# DRS4_ADC.net
KiCad netlist of a schematic drawn in Altium Designer
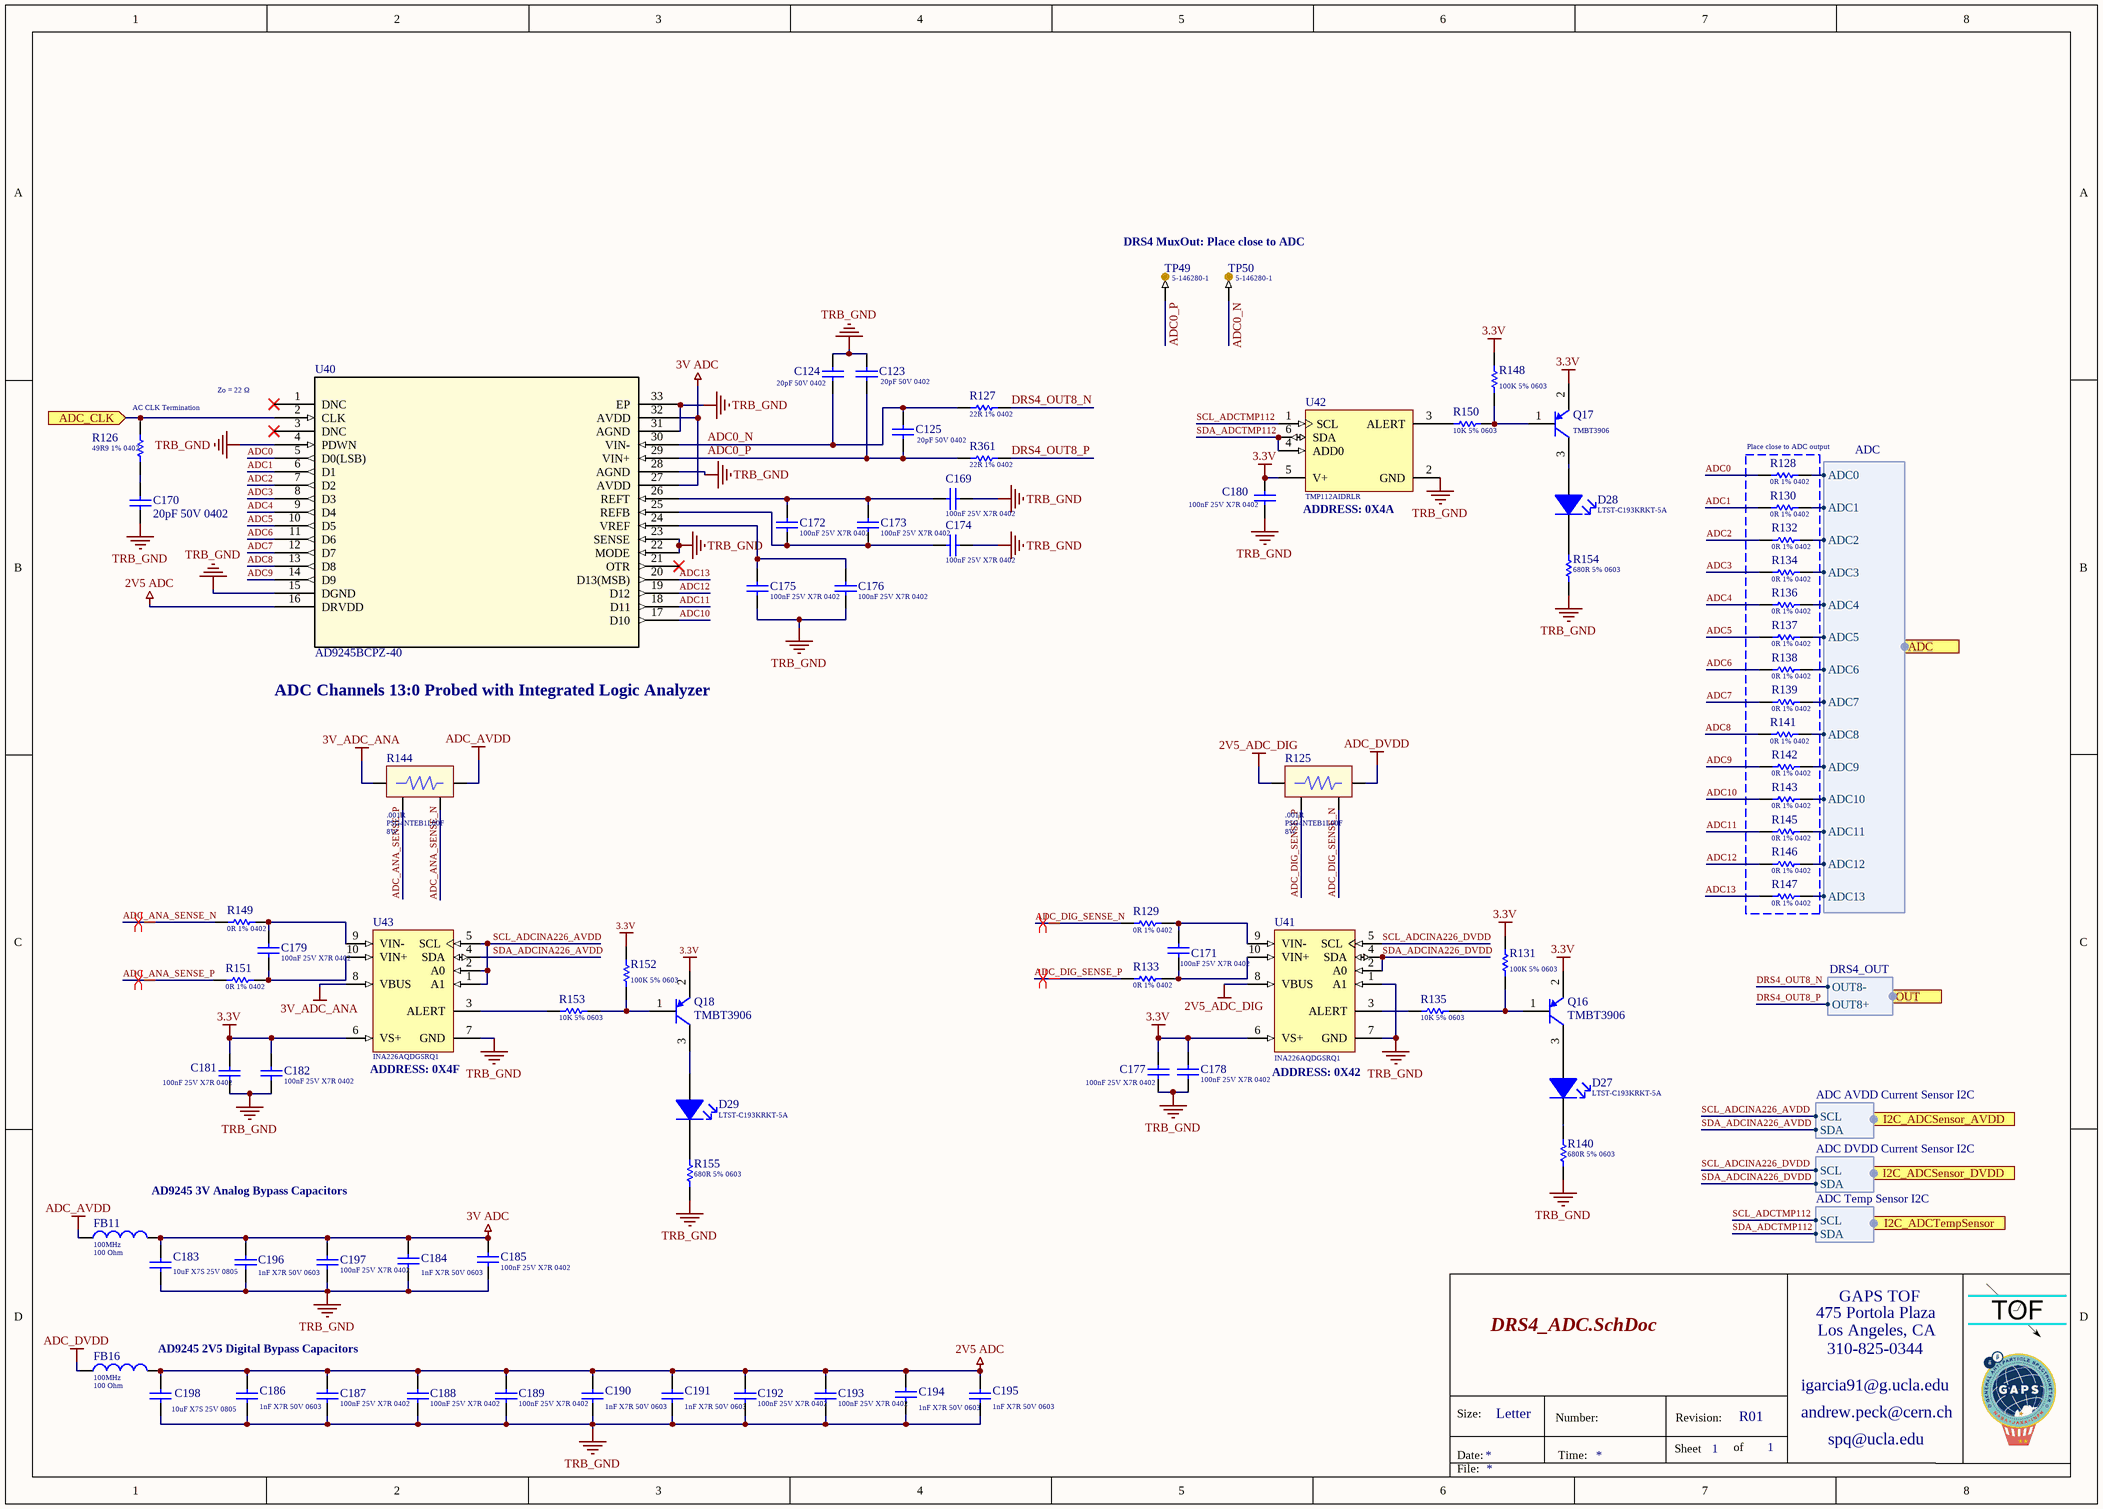
[diagram p0: DRS4_ADC.SchDoc]

(export (version "E")
  (design (tool "Eeschema 10.0.6"))
  (components
    (comp (ref "C123")
      (value "Cap_Murata_GJM1555C1H200GB01D_20pF")
      (footprint "Cap_Murata_GJM1555C1H200GB01D_20pF")
      (description "Multilayer Ceramic Capacitors MLCC - SMD/SMT 0402 20pF 50Volts C0G 2%")
      (fields (field (name "CAPACITANCE") "20pF 50V 0402"))
      (libsource (lib "Cap_Murata_GJM1555C1H200GB01D_20pF") (part "Cap_Murata_GJM1555C1H200GB01D_20pF"))
    )
    (comp (ref "C124")
      (value "Cap_Murata_GJM1555C1H200GB01D_20pF")
      (footprint "Cap_Murata_GJM1555C1H200GB01D_20pF")
      (description "Multilayer Ceramic Capacitors MLCC - SMD/SMT 0402 20pF 50Volts C0G 2%")
      (fields (field (name "CAPACITANCE") "20pF 50V 0402"))
      (libsource (lib "Cap_Murata_GJM1555C1H200GB01D_20pF") (part "Cap_Murata_GJM1555C1H200GB01D_20pF"))
    )
    (comp (ref "C125")
      (value "Cap_Murata_GJM1555C1H200GB01D_20pF")
      (footprint "Cap_Murata_GJM1555C1H200GB01D_20pF")
      (description "Multilayer Ceramic Capacitors MLCC - SMD/SMT 0402 20pF 50Volts C0G 2%")
      (fields (field (name "CAPACITANCE") "20pF 50V 0402"))
      (libsource (lib "Cap_Murata_GJM1555C1H200GB01D_20pF") (part "Cap_Murata_GJM1555C1H200GB01D_20pF"))
    )
    (comp (ref "C169")
      (value "Cap_Taiyo_Yuden_TMK105B7104KV-FR_100nF")
      (footprint "Cap_Taiyo_Yuden_TMK105B7104KV-FR_100nF")
      (description "CAP CER 100nF 25V X7R 0402")
      (fields (field (name "CAPACITANCE") "100nF 25V X7R 0402"))
      (libsource (lib "Cap_Taiyo_Yuden_TMK105B7104KV-FR_100nF") (part "Cap_Taiyo_Yuden_TMK105B7104KV-FR_100nF"))
    )
    (comp (ref "C170")
      (value "Cap_Murata_GJM1555C1H200GB01D_20pF")
      (footprint "Cap_Murata_GJM1555C1H200GB01D_20pF")
      (description "Multilayer Ceramic Capacitors MLCC - SMD/SMT 0402 20pF 50Volts C0G 2%")
      (fields (field (name "CAPACITANCE") "20pF 50V 0402"))
      (libsource (lib "Cap_Murata_GJM1555C1H200GB01D_20pF") (part "Cap_Murata_GJM1555C1H200GB01D_20pF"))
    )
    (comp (ref "C171")
      (value "Cap_Taiyo_Yuden_TMK105B7104KV-FR_100nF")
      (footprint "Cap_Taiyo_Yuden_TMK105B7104KV-FR_100nF")
      (description "CAP CER 100nF 25V X7R 0402")
      (fields (field (name "CAPACITANCE") "100nF 25V X7R 0402"))
      (libsource (lib "Cap_Taiyo_Yuden_TMK105B7104KV-FR_100nF") (part "Cap_Taiyo_Yuden_TMK105B7104KV-FR_100nF"))
    )
    (comp (ref "C172")
      (value "Cap_Taiyo_Yuden_TMK105B7104KV-FR_100nF")
      (footprint "Cap_Taiyo_Yuden_TMK105B7104KV-FR_100nF")
      (description "CAP CER 100nF 25V X7R 0402")
      (fields (field (name "CAPACITANCE") "100nF 25V X7R 0402"))
      (libsource (lib "Cap_Taiyo_Yuden_TMK105B7104KV-FR_100nF") (part "Cap_Taiyo_Yuden_TMK105B7104KV-FR_100nF"))
    )
    (comp (ref "C173")
      (value "Cap_Taiyo_Yuden_TMK105B7104KV-FR_100nF")
      (footprint "Cap_Taiyo_Yuden_TMK105B7104KV-FR_100nF")
      (description "CAP CER 100nF 25V X7R 0402")
      (fields (field (name "CAPACITANCE") "100nF 25V X7R 0402"))
      (libsource (lib "Cap_Taiyo_Yuden_TMK105B7104KV-FR_100nF") (part "Cap_Taiyo_Yuden_TMK105B7104KV-FR_100nF"))
    )
    (comp (ref "C174")
      (value "Cap_Taiyo_Yuden_TMK105B7104KV-FR_100nF")
      (footprint "Cap_Taiyo_Yuden_TMK105B7104KV-FR_100nF")
      (description "CAP CER 100nF 25V X7R 0402")
      (fields (field (name "CAPACITANCE") "100nF 25V X7R 0402"))
      (libsource (lib "Cap_Taiyo_Yuden_TMK105B7104KV-FR_100nF") (part "Cap_Taiyo_Yuden_TMK105B7104KV-FR_100nF"))
    )
    (comp (ref "C175")
      (value "Cap_Taiyo_Yuden_TMK105B7104KV-FR_100nF")
      (footprint "Cap_Taiyo_Yuden_TMK105B7104KV-FR_100nF")
      (description "CAP CER 100nF 25V X7R 0402")
      (fields (field (name "CAPACITANCE") "100nF 25V X7R 0402"))
      (libsource (lib "Cap_Taiyo_Yuden_TMK105B7104KV-FR_100nF") (part "Cap_Taiyo_Yuden_TMK105B7104KV-FR_100nF"))
    )
    (comp (ref "C176")
      (value "Cap_Taiyo_Yuden_TMK105B7104KV-FR_100nF")
      (footprint "Cap_Taiyo_Yuden_TMK105B7104KV-FR_100nF")
      (description "CAP CER 100nF 25V X7R 0402")
      (fields (field (name "CAPACITANCE") "100nF 25V X7R 0402"))
      (libsource (lib "Cap_Taiyo_Yuden_TMK105B7104KV-FR_100nF") (part "Cap_Taiyo_Yuden_TMK105B7104KV-FR_100nF"))
    )
    (comp (ref "C177")
      (value "Cap_Taiyo_Yuden_TMK105B7104KV-FR_100nF")
      (footprint "Cap_Taiyo_Yuden_TMK105B7104KV-FR_100nF")
      (description "CAP CER 100nF 25V X7R 0402")
      (fields (field (name "CAPACITANCE") "100nF 25V X7R 0402"))
      (libsource (lib "Cap_Taiyo_Yuden_TMK105B7104KV-FR_100nF") (part "Cap_Taiyo_Yuden_TMK105B7104KV-FR_100nF"))
    )
    (comp (ref "C178")
      (value "Cap_Taiyo_Yuden_TMK105B7104KV-FR_100nF")
      (footprint "Cap_Taiyo_Yuden_TMK105B7104KV-FR_100nF")
      (description "CAP CER 100nF 25V X7R 0402")
      (fields (field (name "CAPACITANCE") "100nF 25V X7R 0402"))
      (libsource (lib "Cap_Taiyo_Yuden_TMK105B7104KV-FR_100nF") (part "Cap_Taiyo_Yuden_TMK105B7104KV-FR_100nF"))
    )
    (comp (ref "C179")
      (value "Cap_Taiyo_Yuden_TMK105B7104KV-FR_100nF")
      (footprint "Cap_Taiyo_Yuden_TMK105B7104KV-FR_100nF")
      (description "CAP CER 100nF 25V X7R 0402")
      (fields (field (name "CAPACITANCE") "100nF 25V X7R 0402"))
      (libsource (lib "Cap_Taiyo_Yuden_TMK105B7104KV-FR_100nF") (part "Cap_Taiyo_Yuden_TMK105B7104KV-FR_100nF"))
    )
    (comp (ref "C180")
      (value "Cap_Taiyo_Yuden_TMK105B7104KV-FR_100nF")
      (footprint "Cap_Taiyo_Yuden_TMK105B7104KV-FR_100nF")
      (description "CAP CER 100nF 25V X7R 0402")
      (fields (field (name "CAPACITANCE") "100nF 25V X7R 0402"))
      (libsource (lib "Cap_Taiyo_Yuden_TMK105B7104KV-FR_100nF") (part "Cap_Taiyo_Yuden_TMK105B7104KV-FR_100nF"))
    )
    (comp (ref "C181")
      (value "Cap_Taiyo_Yuden_TMK105B7104KV-FR_100nF")
      (footprint "Cap_Taiyo_Yuden_TMK105B7104KV-FR_100nF")
      (description "CAP CER 100nF 25V X7R 0402")
      (fields (field (name "CAPACITANCE") "100nF 25V X7R 0402"))
      (libsource (lib "Cap_Taiyo_Yuden_TMK105B7104KV-FR_100nF") (part "Cap_Taiyo_Yuden_TMK105B7104KV-FR_100nF"))
    )
    (comp (ref "C182")
      (value "Cap_Taiyo_Yuden_TMK105B7104KV-FR_100nF")
      (footprint "Cap_Taiyo_Yuden_TMK105B7104KV-FR_100nF")
      (description "CAP CER 100nF 25V X7R 0402")
      (fields (field (name "CAPACITANCE") "100nF 25V X7R 0402"))
      (libsource (lib "Cap_Taiyo_Yuden_TMK105B7104KV-FR_100nF") (part "Cap_Taiyo_Yuden_TMK105B7104KV-FR_100nF"))
    )
    (comp (ref "C183")
      (value "Cap_Murata_ GRM21BC71E106ME11L_10uF")
      (footprint "Cap_Murata_ GRM21BC71E106ME11L_10uF")
      (description "CAP CER 10uF 25V X7R 0805")
      (fields (field (name "CAPACITANCE") "10uF X7S 25V 0805"))
      (libsource (lib "Cap_Murata_ GRM21BC71E106ME11L_10uF") (part "Cap_Murata_ GRM21BC71E106ME11L_10uF"))
    )
    (comp (ref "C184")
      (value "Cap_Kemet_C0603C102J5RACAUTO_1nF")
      (footprint "Cap_Kemet_C0603C102J5RACAUTO_1nF")
      (description "CAP CER 1nF 50V X7R 0603")
      (fields (field (name "CAPACITANCE") "1nF X7R 50V 0603"))
      (libsource (lib "Cap_Kemet_C0603C102J5RACAUTO_1nF") (part "Cap_Kemet_C0603C102J5RACAUTO_1nF"))
    )
    (comp (ref "C185")
      (value "Cap_Taiyo_Yuden_TMK105B7104KV-FR_100nF")
      (footprint "Cap_Taiyo_Yuden_TMK105B7104KV-FR_100nF")
      (description "CAP CER 100nF 25V X7R 0402")
      (fields (field (name "CAPACITANCE") "100nF 25V X7R 0402"))
      (libsource (lib "Cap_Taiyo_Yuden_TMK105B7104KV-FR_100nF") (part "Cap_Taiyo_Yuden_TMK105B7104KV-FR_100nF"))
    )
    (comp (ref "C186")
      (value "Cap_Kemet_C0603C102J5RACAUTO_1nF")
      (footprint "Cap_Kemet_C0603C102J5RACAUTO_1nF")
      (description "CAP CER 1nF 50V X7R 0603")
      (fields (field (name "CAPACITANCE") "1nF X7R 50V 0603"))
      (libsource (lib "Cap_Kemet_C0603C102J5RACAUTO_1nF") (part "Cap_Kemet_C0603C102J5RACAUTO_1nF"))
    )
    (comp (ref "C187")
      (value "Cap_Taiyo_Yuden_TMK105B7104KV-FR_100nF")
      (footprint "Cap_Taiyo_Yuden_TMK105B7104KV-FR_100nF")
      (description "CAP CER 100nF 25V X7R 0402")
      (fields (field (name "CAPACITANCE") "100nF 25V X7R 0402"))
      (libsource (lib "Cap_Taiyo_Yuden_TMK105B7104KV-FR_100nF") (part "Cap_Taiyo_Yuden_TMK105B7104KV-FR_100nF"))
    )
    (comp (ref "C188")
      (value "Cap_Taiyo_Yuden_TMK105B7104KV-FR_100nF")
      (footprint "Cap_Taiyo_Yuden_TMK105B7104KV-FR_100nF")
      (description "CAP CER 100nF 25V X7R 0402")
      (fields (field (name "CAPACITANCE") "100nF 25V X7R 0402"))
      (libsource (lib "Cap_Taiyo_Yuden_TMK105B7104KV-FR_100nF") (part "Cap_Taiyo_Yuden_TMK105B7104KV-FR_100nF"))
    )
    (comp (ref "C189")
      (value "Cap_Taiyo_Yuden_TMK105B7104KV-FR_100nF")
      (footprint "Cap_Taiyo_Yuden_TMK105B7104KV-FR_100nF")
      (description "CAP CER 100nF 25V X7R 0402")
      (fields (field (name "CAPACITANCE") "100nF 25V X7R 0402"))
      (libsource (lib "Cap_Taiyo_Yuden_TMK105B7104KV-FR_100nF") (part "Cap_Taiyo_Yuden_TMK105B7104KV-FR_100nF"))
    )
    (comp (ref "C190")
      (value "Cap_Kemet_C0603C102J5RACAUTO_1nF")
      (footprint "Cap_Kemet_C0603C102J5RACAUTO_1nF")
      (description "CAP CER 1nF 50V X7R 0603")
      (fields (field (name "CAPACITANCE") "1nF X7R 50V 0603"))
      (libsource (lib "Cap_Kemet_C0603C102J5RACAUTO_1nF") (part "Cap_Kemet_C0603C102J5RACAUTO_1nF"))
    )
    (comp (ref "C191")
      (value "Cap_Kemet_C0603C102J5RACAUTO_1nF")
      (footprint "Cap_Kemet_C0603C102J5RACAUTO_1nF")
      (description "CAP CER 1nF 50V X7R 0603")
      (fields (field (name "CAPACITANCE") "1nF X7R 50V 0603"))
      (libsource (lib "Cap_Kemet_C0603C102J5RACAUTO_1nF") (part "Cap_Kemet_C0603C102J5RACAUTO_1nF"))
    )
    (comp (ref "C192")
      (value "Cap_Taiyo_Yuden_TMK105B7104KV-FR_100nF")
      (footprint "Cap_Taiyo_Yuden_TMK105B7104KV-FR_100nF")
      (description "CAP CER 100nF 25V X7R 0402")
      (fields (field (name "CAPACITANCE") "100nF 25V X7R 0402"))
      (libsource (lib "Cap_Taiyo_Yuden_TMK105B7104KV-FR_100nF") (part "Cap_Taiyo_Yuden_TMK105B7104KV-FR_100nF"))
    )
    (comp (ref "C193")
      (value "Cap_Taiyo_Yuden_TMK105B7104KV-FR_100nF")
      (footprint "Cap_Taiyo_Yuden_TMK105B7104KV-FR_100nF")
      (description "CAP CER 100nF 25V X7R 0402")
      (fields (field (name "CAPACITANCE") "100nF 25V X7R 0402"))
      (libsource (lib "Cap_Taiyo_Yuden_TMK105B7104KV-FR_100nF") (part "Cap_Taiyo_Yuden_TMK105B7104KV-FR_100nF"))
    )
    (comp (ref "C194")
      (value "Cap_Kemet_C0603C102J5RACAUTO_1nF")
      (footprint "Cap_Kemet_C0603C102J5RACAUTO_1nF")
      (description "CAP CER 1nF 50V X7R 0603")
      (fields (field (name "CAPACITANCE") "1nF X7R 50V 0603"))
      (libsource (lib "Cap_Kemet_C0603C102J5RACAUTO_1nF") (part "Cap_Kemet_C0603C102J5RACAUTO_1nF"))
    )
    (comp (ref "C195")
      (value "Cap_Kemet_C0603C102J5RACAUTO_1nF")
      (footprint "Cap_Kemet_C0603C102J5RACAUTO_1nF")
      (description "CAP CER 1nF 50V X7R 0603")
      (fields (field (name "CAPACITANCE") "1nF X7R 50V 0603"))
      (libsource (lib "Cap_Kemet_C0603C102J5RACAUTO_1nF") (part "Cap_Kemet_C0603C102J5RACAUTO_1nF"))
    )
    (comp (ref "C196")
      (value "Cap_Kemet_C0603C102J5RACAUTO_1nF")
      (footprint "Cap_Kemet_C0603C102J5RACAUTO_1nF")
      (description "CAP CER 1nF 50V X7R 0603")
      (fields (field (name "CAPACITANCE") "1nF X7R 50V 0603"))
      (libsource (lib "Cap_Kemet_C0603C102J5RACAUTO_1nF") (part "Cap_Kemet_C0603C102J5RACAUTO_1nF"))
    )
    (comp (ref "C197")
      (value "Cap_Taiyo_Yuden_TMK105B7104KV-FR_100nF")
      (footprint "Cap_Taiyo_Yuden_TMK105B7104KV-FR_100nF")
      (description "CAP CER 100nF 25V X7R 0402")
      (fields (field (name "CAPACITANCE") "100nF 25V X7R 0402"))
      (libsource (lib "Cap_Taiyo_Yuden_TMK105B7104KV-FR_100nF") (part "Cap_Taiyo_Yuden_TMK105B7104KV-FR_100nF"))
    )
    (comp (ref "C198")
      (value "Cap_Murata_ GRM21BC71E106ME11L_10uF")
      (footprint "Cap_Murata_ GRM21BC71E106ME11L_10uF")
      (description "CAP CER 10uF 25V X7R 0805")
      (fields (field (name "CAPACITANCE") "10uF X7S 25V 0805"))
      (libsource (lib "Cap_Murata_ GRM21BC71E106ME11L_10uF") (part "Cap_Murata_ GRM21BC71E106ME11L_10uF"))
    )
    (comp (ref "D27")
      (value "LTST-C193KRKT-5A")
      (footprint "Led_Lite-On_LTST-C193KGKT-5A_Red")
      (description "Standard LEDs - SMD Red 470nm 28mcd 20mA")
      (fields (field (name "SERIES") "LTST-C193KRKT-5A"))
      (libsource (lib "Led_Lite-On_LTST-C193KGKT-5A_Red") (part "Led_Lite-On_LTST-C193KGKT-5A_Red"))
    )
    (comp (ref "D28")
      (value "LTST-C193KRKT-5A")
      (footprint "Led_Lite-On_LTST-C193KGKT-5A_Red")
      (description "Standard LEDs - SMD Red 470nm 28mcd 20mA")
      (fields (field (name "SERIES") "LTST-C193KRKT-5A"))
      (libsource (lib "Led_Lite-On_LTST-C193KGKT-5A_Red") (part "Led_Lite-On_LTST-C193KGKT-5A_Red"))
    )
    (comp (ref "D29")
      (value "LTST-C193KRKT-5A")
      (footprint "Led_Lite-On_LTST-C193KGKT-5A_Red")
      (description "Standard LEDs - SMD Red 470nm 28mcd 20mA")
      (fields (field (name "SERIES") "LTST-C193KRKT-5A"))
      (libsource (lib "Led_Lite-On_LTST-C193KGKT-5A_Red") (part "Led_Lite-On_LTST-C193KGKT-5A_Red"))
    )
    (comp (ref "FB11")
      (value "742792731")
      (footprint "FB_Wurth_Electronics_742792731_100Ohms")
      (description "FB SMD 100 OHM 25% 1.2A 0402")
      (fields (field (name "MEASURING FREQUENCY") "100MHz") (field (name "IMPEDANCE") "100 Ohm"))
      (libsource (lib "FB_Wurth_Electronics_742792731_100Ohms") (part "FB_Wurth_Electronics_742792731_100Ohms"))
    )
    (comp (ref "FB16")
      (value "742792731")
      (footprint "FB_Wurth_Electronics_742792731_100Ohms")
      (description "FB SMD 100 OHM 25% 1.2A 0402")
      (fields (field (name "MEASURING FREQUENCY") "100MHz") (field (name "IMPEDANCE") "100 Ohm"))
      (libsource (lib "FB_Wurth_Electronics_742792731_100Ohms") (part "FB_Wurth_Electronics_742792731_100Ohms"))
    )
    (comp (ref "Q16")
      (value "BJT_PNP_Toshiba_TMBT3906")
      (footprint "BJT_PNP_Toshiba_TMBT3906")
      (description "Bipolar Transistors - BJT Transistor for Low Freq. Amplification")
      (fields (field (name "SERIES") "TMBT3906"))
      (libsource (lib "BJT_PNP_Toshiba_TMBT3906") (part "BJT_PNP_Toshiba_TMBT3906"))
    )
    (comp (ref "Q17")
      (value "BJT_PNP_Toshiba_TMBT3906")
      (footprint "BJT_PNP_Toshiba_TMBT3906")
      (description "Bipolar Transistors - BJT Transistor for Low Freq. Amplification")
      (fields (field (name "SERIES") "TMBT3906"))
      (libsource (lib "BJT_PNP_Toshiba_TMBT3906") (part "BJT_PNP_Toshiba_TMBT3906"))
    )
    (comp (ref "Q18")
      (value "BJT_PNP_Toshiba_TMBT3906")
      (footprint "BJT_PNP_Toshiba_TMBT3906")
      (description "Bipolar Transistors - BJT Transistor for Low Freq. Amplification")
      (fields (field (name "SERIES") "TMBT3906"))
      (libsource (lib "BJT_PNP_Toshiba_TMBT3906") (part "BJT_PNP_Toshiba_TMBT3906"))
    )
    (comp (ref "R125")
      (value "SRes_KOA_PSG4NTEB1L00F_1mOhm")
      (footprint "SRes_KOA_PSG4NTEB1L00F_1mOhm")
      (description "Current Sense Resistors - SMD 1mOhm 8W 1% 50ppm AEC-Q200 Power Shunt")
      (fields
        (field (name "RESISTANCE") ".001R")
        (field (name "SERIES") "PSG4NTEB1L00F")
        (field (name "PARAMETER 1") "8W")
      )
      (libsource (lib "SRes_KOA_PSG4NTEB1L00F_1mOhm") (part "SRes_KOA_PSG4NTEB1L00F_1mOhm"))
    )
    (comp (ref "R126")
      (value "49R9 1% 0402")
      (footprint "RESC0402(1005)_L")
      (description "49R9 0.063W 1% 0402 (1005 Metric)  SMD")
      (fields (field (name "POWER") "0.063 W") (field (name "TOLERANCE") "1 %"))
      (libsource (lib "Altium Content Vault") (part "RES"))
    )
    (comp (ref "R127")
      (value "22R 1% 0402")
      (footprint "RESC0402(1005)_L")
      (description "22R 0.063W 1% 0402 (1005 Metric)  SMD")
      (fields (field (name "TOLERANCE") "1 %") (field (name "POWER") "0.063 W"))
      (libsource (lib "Altium Content Vault") (part "RES"))
    )
    (comp (ref "R128")
      (value "Res_Vishay_CRCW04020000Z0EDC_0_Ohm")
      (footprint "Res_Vishay_CRCW04020000Z0EDC_0_Ohm")
      (description "0R 0.062W 1% 0402 (1005 Metric)  SMD")
      (fields (field (name "RESISTANCE") "0R 1% 0402"))
      (libsource (lib "Res_Vishay_CRCW04020000Z0EDC_0_Ohm") (part "Res_Vishay_CRCW04020000Z0EDC_0_Ohm"))
    )
    (comp (ref "R129")
      (value "Res_Vishay_CRCW04020000Z0EDC_0_Ohm")
      (footprint "Res_Vishay_CRCW04020000Z0EDC_0_Ohm")
      (description "0R 0.062W 1% 0402 (1005 Metric)  SMD")
      (fields (field (name "RESISTANCE") "0R 1% 0402"))
      (libsource (lib "Res_Vishay_CRCW04020000Z0EDC_0_Ohm") (part "Res_Vishay_CRCW04020000Z0EDC_0_Ohm"))
    )
    (comp (ref "R130")
      (value "Res_Vishay_CRCW04020000Z0EDC_0_Ohm")
      (footprint "Res_Vishay_CRCW04020000Z0EDC_0_Ohm")
      (description "0R 0.062W 1% 0402 (1005 Metric)  SMD")
      (fields (field (name "RESISTANCE") "0R 1% 0402"))
      (libsource (lib "Res_Vishay_CRCW04020000Z0EDC_0_Ohm") (part "Res_Vishay_CRCW04020000Z0EDC_0_Ohm"))
    )
    (comp (ref "R131")
      (value "100K 5% 0603")
      (footprint "RESC0603(1608)_N")
      (description "100K 0.1W 5% 0603 (1608 Metric)  SMD")
      (fields (field (name "TOLERANCE") "5 %") (field (name "POWER") "0.1 W"))
      (libsource (lib "Altium Content Vault") (part "RES"))
    )
    (comp (ref "R132")
      (value "Res_Vishay_CRCW04020000Z0EDC_0_Ohm")
      (footprint "Res_Vishay_CRCW04020000Z0EDC_0_Ohm")
      (description "0R 0.062W 1% 0402 (1005 Metric)  SMD")
      (fields (field (name "RESISTANCE") "0R 1% 0402"))
      (libsource (lib "Res_Vishay_CRCW04020000Z0EDC_0_Ohm") (part "Res_Vishay_CRCW04020000Z0EDC_0_Ohm"))
    )
    (comp (ref "R133")
      (value "Res_Vishay_CRCW04020000Z0EDC_0_Ohm")
      (footprint "Res_Vishay_CRCW04020000Z0EDC_0_Ohm")
      (description "0R 0.062W 1% 0402 (1005 Metric)  SMD")
      (fields (field (name "RESISTANCE") "0R 1% 0402"))
      (libsource (lib "Res_Vishay_CRCW04020000Z0EDC_0_Ohm") (part "Res_Vishay_CRCW04020000Z0EDC_0_Ohm"))
    )
    (comp (ref "R134")
      (value "Res_Vishay_CRCW04020000Z0EDC_0_Ohm")
      (footprint "Res_Vishay_CRCW04020000Z0EDC_0_Ohm")
      (description "0R 0.062W 1% 0402 (1005 Metric)  SMD")
      (fields (field (name "RESISTANCE") "0R 1% 0402"))
      (libsource (lib "Res_Vishay_CRCW04020000Z0EDC_0_Ohm") (part "Res_Vishay_CRCW04020000Z0EDC_0_Ohm"))
    )
    (comp (ref "R135")
      (value "10K 5% 0603")
      (footprint "RESC0603(1608)_L")
      (description "10K 0.1W 5% 0603 (1608 Metric)  SMD")
      (fields (field (name "TOLERANCE") "5 %") (field (name "POWER") "0.1 W"))
      (libsource (lib "Altium Content Vault") (part "RES"))
    )
    (comp (ref "R136")
      (value "Res_Vishay_CRCW04020000Z0EDC_0_Ohm")
      (footprint "Res_Vishay_CRCW04020000Z0EDC_0_Ohm")
      (description "0R 0.062W 1% 0402 (1005 Metric)  SMD")
      (fields (field (name "RESISTANCE") "0R 1% 0402"))
      (libsource (lib "Res_Vishay_CRCW04020000Z0EDC_0_Ohm") (part "Res_Vishay_CRCW04020000Z0EDC_0_Ohm"))
    )
    (comp (ref "R137")
      (value "Res_Vishay_CRCW04020000Z0EDC_0_Ohm")
      (footprint "Res_Vishay_CRCW04020000Z0EDC_0_Ohm")
      (description "0R 0.062W 1% 0402 (1005 Metric)  SMD")
      (fields (field (name "RESISTANCE") "0R 1% 0402"))
      (libsource (lib "Res_Vishay_CRCW04020000Z0EDC_0_Ohm") (part "Res_Vishay_CRCW04020000Z0EDC_0_Ohm"))
    )
    (comp (ref "R138")
      (value "Res_Vishay_CRCW04020000Z0EDC_0_Ohm")
      (footprint "Res_Vishay_CRCW04020000Z0EDC_0_Ohm")
      (description "0R 0.062W 1% 0402 (1005 Metric)  SMD")
      (fields (field (name "RESISTANCE") "0R 1% 0402"))
      (libsource (lib "Res_Vishay_CRCW04020000Z0EDC_0_Ohm") (part "Res_Vishay_CRCW04020000Z0EDC_0_Ohm"))
    )
    (comp (ref "R139")
      (value "Res_Vishay_CRCW04020000Z0EDC_0_Ohm")
      (footprint "Res_Vishay_CRCW04020000Z0EDC_0_Ohm")
      (description "0R 0.062W 1% 0402 (1005 Metric)  SMD")
      (fields (field (name "RESISTANCE") "0R 1% 0402"))
      (libsource (lib "Res_Vishay_CRCW04020000Z0EDC_0_Ohm") (part "Res_Vishay_CRCW04020000Z0EDC_0_Ohm"))
    )
    (comp (ref "R140")
      (value "680R 5% 0603")
      (footprint "RESC0603(1608)_L")
      (description "680R 0.1W 5% 0603 (1608 Metric)  SMD")
      (fields (field (name "TOLERANCE") "5 %") (field (name "POWER") "0.1 W"))
      (libsource (lib "Altium Content Vault") (part "RES"))
    )
    (comp (ref "R141")
      (value "Res_Vishay_CRCW04020000Z0EDC_0_Ohm")
      (footprint "Res_Vishay_CRCW04020000Z0EDC_0_Ohm")
      (description "0R 0.062W 1% 0402 (1005 Metric)  SMD")
      (fields (field (name "RESISTANCE") "0R 1% 0402"))
      (libsource (lib "Res_Vishay_CRCW04020000Z0EDC_0_Ohm") (part "Res_Vishay_CRCW04020000Z0EDC_0_Ohm"))
    )
    (comp (ref "R142")
      (value "Res_Vishay_CRCW04020000Z0EDC_0_Ohm")
      (footprint "Res_Vishay_CRCW04020000Z0EDC_0_Ohm")
      (description "0R 0.062W 1% 0402 (1005 Metric)  SMD")
      (fields (field (name "RESISTANCE") "0R 1% 0402"))
      (libsource (lib "Res_Vishay_CRCW04020000Z0EDC_0_Ohm") (part "Res_Vishay_CRCW04020000Z0EDC_0_Ohm"))
    )
    (comp (ref "R143")
      (value "Res_Vishay_CRCW04020000Z0EDC_0_Ohm")
      (footprint "Res_Vishay_CRCW04020000Z0EDC_0_Ohm")
      (description "0R 0.062W 1% 0402 (1005 Metric)  SMD")
      (fields (field (name "RESISTANCE") "0R 1% 0402"))
      (libsource (lib "Res_Vishay_CRCW04020000Z0EDC_0_Ohm") (part "Res_Vishay_CRCW04020000Z0EDC_0_Ohm"))
    )
    (comp (ref "R144")
      (value "SRes_KOA_PSG4NTEB1L00F_1mOhm")
      (footprint "SRes_KOA_PSG4NTEB1L00F_1mOhm")
      (description "Current Sense Resistors - SMD 1mOhm 8W 1% 50ppm AEC-Q200 Power Shunt")
      (fields
        (field (name "RESISTANCE") ".001R")
        (field (name "SERIES") "PSG4NTEB1L00F")
        (field (name "PARAMETER 1") "8W")
      )
      (libsource (lib "SRes_KOA_PSG4NTEB1L00F_1mOhm") (part "SRes_KOA_PSG4NTEB1L00F_1mOhm"))
    )
    (comp (ref "R145")
      (value "Res_Vishay_CRCW04020000Z0EDC_0_Ohm")
      (footprint "Res_Vishay_CRCW04020000Z0EDC_0_Ohm")
      (description "0R 0.062W 1% 0402 (1005 Metric)  SMD")
      (fields (field (name "RESISTANCE") "0R 1% 0402"))
      (libsource (lib "Res_Vishay_CRCW04020000Z0EDC_0_Ohm") (part "Res_Vishay_CRCW04020000Z0EDC_0_Ohm"))
    )
    (comp (ref "R146")
      (value "Res_Vishay_CRCW04020000Z0EDC_0_Ohm")
      (footprint "Res_Vishay_CRCW04020000Z0EDC_0_Ohm")
      (description "0R 0.062W 1% 0402 (1005 Metric)  SMD")
      (fields (field (name "RESISTANCE") "0R 1% 0402"))
      (libsource (lib "Res_Vishay_CRCW04020000Z0EDC_0_Ohm") (part "Res_Vishay_CRCW04020000Z0EDC_0_Ohm"))
    )
    (comp (ref "R147")
      (value "Res_Vishay_CRCW04020000Z0EDC_0_Ohm")
      (footprint "Res_Vishay_CRCW04020000Z0EDC_0_Ohm")
      (description "0R 0.062W 1% 0402 (1005 Metric)  SMD")
      (fields (field (name "RESISTANCE") "0R 1% 0402"))
      (libsource (lib "Res_Vishay_CRCW04020000Z0EDC_0_Ohm") (part "Res_Vishay_CRCW04020000Z0EDC_0_Ohm"))
    )
    (comp (ref "R148")
      (value "100K 5% 0603")
      (footprint "RESC0603(1608)_N")
      (description "100K 0.1W 5% 0603 (1608 Metric)  SMD")
      (fields (field (name "TOLERANCE") "5 %") (field (name "POWER") "0.1 W"))
      (libsource (lib "Altium Content Vault") (part "RES"))
    )
    (comp (ref "R149")
      (value "Res_Vishay_CRCW04020000Z0EDC_0_Ohm")
      (footprint "Res_Vishay_CRCW04020000Z0EDC_0_Ohm")
      (description "0R 0.062W 1% 0402 (1005 Metric)  SMD")
      (fields (field (name "RESISTANCE") "0R 1% 0402"))
      (libsource (lib "Res_Vishay_CRCW04020000Z0EDC_0_Ohm") (part "Res_Vishay_CRCW04020000Z0EDC_0_Ohm"))
    )
    (comp (ref "R150")
      (value "10K 5% 0603")
      (footprint "RESC0603(1608)_L")
      (description "10K 0.1W 5% 0603 (1608 Metric)  SMD")
      (fields (field (name "TOLERANCE") "5 %") (field (name "POWER") "0.1 W"))
      (libsource (lib "Altium Content Vault") (part "RES"))
    )
    (comp (ref "R151")
      (value "Res_Vishay_CRCW04020000Z0EDC_0_Ohm")
      (footprint "Res_Vishay_CRCW04020000Z0EDC_0_Ohm")
      (description "0R 0.062W 1% 0402 (1005 Metric)  SMD")
      (fields (field (name "RESISTANCE") "0R 1% 0402"))
      (libsource (lib "Res_Vishay_CRCW04020000Z0EDC_0_Ohm") (part "Res_Vishay_CRCW04020000Z0EDC_0_Ohm"))
    )
    (comp (ref "R152")
      (value "100K 5% 0603")
      (footprint "RESC0603(1608)_N")
      (description "100K 0.1W 5% 0603 (1608 Metric)  SMD")
      (fields (field (name "TOLERANCE") "5 %") (field (name "POWER") "0.1 W"))
      (libsource (lib "Altium Content Vault") (part "RES"))
    )
    (comp (ref "R153")
      (value "10K 5% 0603")
      (footprint "RESC0603(1608)_L")
      (description "10K 0.1W 5% 0603 (1608 Metric)  SMD")
      (fields (field (name "TOLERANCE") "5 %") (field (name "POWER") "0.1 W"))
      (libsource (lib "Altium Content Vault") (part "RES"))
    )
    (comp (ref "R154")
      (value "680R 5% 0603")
      (footprint "RESC0603(1608)_L")
      (description "680R 0.1W 5% 0603 (1608 Metric)  SMD")
      (fields (field (name "TOLERANCE") "5 %") (field (name "POWER") "0.1 W"))
      (libsource (lib "Altium Content Vault") (part "RES"))
    )
    (comp (ref "R155")
      (value "680R 5% 0603")
      (footprint "RESC0603(1608)_L")
      (description "680R 0.1W 5% 0603 (1608 Metric)  SMD")
      (fields (field (name "TOLERANCE") "5 %") (field (name "POWER") "0.1 W"))
      (libsource (lib "Altium Content Vault") (part "RES"))
    )
    (comp (ref "R361")
      (value "22R 1% 0402")
      (footprint "RESC0402(1005)_L")
      (description "22R 0.063W 1% 0402 (1005 Metric)  SMD")
      (fields (field (name "TOLERANCE") "1 %") (field (name "POWER") "0.063 W"))
      (libsource (lib "Altium Content Vault") (part "RES"))
    )
    (comp (ref "TP49")
      (value "TP_TE_Connectivity_5-146280-1_1POS")
      (footprint "TP_TE_Connectivity_5-146280-1_1POS")
      (description "Headers & Wire Housings Unshrouded 1 POS T/H")
      (fields (field (name "SERIES") "5-146280-1"))
      (libsource (lib "TP_TE_Connectivity_5-146280-1_1POS") (part "TP_TE_Connectivity_5-146280-1_1POS"))
    )
    (comp (ref "TP50")
      (value "TP_TE_Connectivity_5-146280-1_1POS")
      (footprint "TP_TE_Connectivity_5-146280-1_1POS")
      (description "Headers & Wire Housings Unshrouded 1 POS T/H")
      (fields (field (name "SERIES") "5-146280-1"))
      (libsource (lib "TP_TE_Connectivity_5-146280-1_1POS") (part "TP_TE_Connectivity_5-146280-1_1POS"))
    )
    (comp (ref "U40")
      (value "AD9245")
      (footprint "CP_32_2")
      (description "Analog to Digital Converters - ADC 14-Bit 40 MSPS 3V")
      (fields (field (name "SERIES") "AD9245BCPZ-40") (field (name "PART") "AD9245BCPZ-40"))
      (libsource (lib "AD9245BCPZ-40") (part "AD9245BCPZ-40"))
    )
    (comp (ref "U41")
      (value "INA226AQDGSRQ1")
      (footprint "INA226AQDGSRQ1")
      (libsource (lib "INA226AQDGSRQ1") (part "INA226AQDGSRQ1"))
    )
    (comp (ref "U42")
      (value "TMP112AIDRLR")
      (footprint "TMP112AIDRLR")
      (description "Board Mount Temperature Sensors Hi-Prec Lo-Pwr Dig Temp Sensor")
      (libsource (lib "TMP112AIDRLR") (part "TMP112AIDRLR"))
    )
    (comp (ref "U43")
      (value "INA226AQDGSRQ1")
      (footprint "INA226AQDGSRQ1")
      (libsource (lib "INA226AQDGSRQ1") (part "INA226AQDGSRQ1"))
    )
  )
  (nets
    (net (code "9") (name "/ADC0") (class "Default")
      (node (ref "R128") (pin "1") (pinfunction "1_1") (pintype "passive"))
      (node (ref "U40") (pin "5") (pinfunction "D0(LSB)_5") (pintype "output"))
    )
    (net (code "10") (name "/ADC0_N") (class "Default")
      (node (ref "C124") (pin "1") (pinfunction "1_1") (pintype "passive"))
      (node (ref "C125") (pin "2") (pinfunction "2_2") (pintype "passive"))
      (node (ref "R127") (pin "2") (pinfunction "2_2") (pintype "passive"))
      (node (ref "TP50") (pin "1") (pinfunction "1_1") (pintype "input"))
      (node (ref "U40") (pin "30") (pinfunction "VIN-_30") (pintype "input"))
    )
    (net (code "11") (name "/ADC0_P") (class "Default")
      (node (ref "C123") (pin "1") (pinfunction "1_1") (pintype "passive"))
      (node (ref "C125") (pin "1") (pinfunction "1_1") (pintype "passive"))
      (node (ref "R361") (pin "2") (pinfunction "2_2") (pintype "passive"))
      (node (ref "TP49") (pin "1") (pinfunction "1_1") (pintype "input"))
      (node (ref "U40") (pin "29") (pinfunction "VIN+_29") (pintype "input"))
    )
    (net (code "12") (name "/ADC1") (class "Default")
      (node (ref "R130") (pin "1") (pinfunction "1_1") (pintype "passive"))
      (node (ref "U40") (pin "6") (pinfunction "D1_6") (pintype "output"))
    )
    (net (code "13") (name "/ADC2") (class "Default")
      (node (ref "R132") (pin "1") (pinfunction "1_1") (pintype "passive"))
      (node (ref "U40") (pin "7") (pinfunction "D2_7") (pintype "output"))
    )
    (net (code "14") (name "/ADC3") (class "Default")
      (node (ref "R134") (pin "1") (pinfunction "1_1") (pintype "passive"))
      (node (ref "U40") (pin "8") (pinfunction "D3_8") (pintype "output"))
    )
    (net (code "15") (name "/ADC4") (class "Default")
      (node (ref "R136") (pin "1") (pinfunction "1_1") (pintype "passive"))
      (node (ref "U40") (pin "9") (pinfunction "D4_9") (pintype "output"))
    )
    (net (code "16") (name "/ADC5") (class "Default")
      (node (ref "R137") (pin "1") (pinfunction "1_1") (pintype "passive"))
      (node (ref "U40") (pin "10") (pinfunction "D5_10") (pintype "output"))
    )
    (net (code "17") (name "/ADC6") (class "Default")
      (node (ref "R138") (pin "1") (pinfunction "1_1") (pintype "passive"))
      (node (ref "U40") (pin "11") (pinfunction "D6_11") (pintype "output"))
    )
    (net (code "18") (name "/ADC7") (class "Default")
      (node (ref "R139") (pin "1") (pinfunction "1_1") (pintype "passive"))
      (node (ref "U40") (pin "12") (pinfunction "D7_12") (pintype "output"))
    )
    (net (code "19") (name "/ADC8") (class "Default")
      (node (ref "R141") (pin "1") (pinfunction "1_1") (pintype "passive"))
      (node (ref "U40") (pin "13") (pinfunction "D8_13") (pintype "output"))
    )
    (net (code "20") (name "/ADC9") (class "Default")
      (node (ref "R142") (pin "1") (pinfunction "1_1") (pintype "passive"))
      (node (ref "U40") (pin "14") (pinfunction "D9_14") (pintype "output"))
    )
    (net (code "21") (name "/ADC10") (class "Default")
      (node (ref "R143") (pin "1") (pinfunction "1_1") (pintype "passive"))
      (node (ref "U40") (pin "17") (pinfunction "D10_17") (pintype "output"))
    )
    (net (code "22") (name "/ADC11") (class "Default")
      (node (ref "R145") (pin "1") (pinfunction "1_1") (pintype "passive"))
      (node (ref "U40") (pin "18") (pinfunction "D11_18") (pintype "output"))
    )
    (net (code "23") (name "/ADC12") (class "Default")
      (node (ref "R146") (pin "1") (pinfunction "1_1") (pintype "passive"))
      (node (ref "U40") (pin "19") (pinfunction "D12_19") (pintype "output"))
    )
    (net (code "24") (name "/ADC13") (class "Default")
      (node (ref "R147") (pin "1") (pinfunction "1_1") (pintype "passive"))
      (node (ref "U40") (pin "20") (pinfunction "D13(MSB)_20") (pintype "output"))
    )
    (net (code "25") (name "/ADC_ANA_SENSE_N") (class "Default")
      (node (ref "R144") (pin "3") (pinfunction "3_3") (pintype "passive"))
      (node (ref "R149") (pin "1") (pinfunction "1_1") (pintype "passive"))
    )
    (net (code "26") (name "/ADC_ANA_SENSE_P") (class "Default")
      (node (ref "R144") (pin "4") (pinfunction "4_4") (pintype "passive"))
      (node (ref "R151") (pin "1") (pinfunction "1_1") (pintype "passive"))
    )
    (net (code "27") (name "/ADC_CLK") (class "Default")
      (node (ref "R126") (pin "2") (pinfunction "2_2") (pintype "passive"))
      (node (ref "U40") (pin "2") (pinfunction "CLK_2") (pintype "input"))
    )
    (net (code "28") (name "/ADC_DIG_SENSE_N") (class "Default")
      (node (ref "R125") (pin "3") (pinfunction "3_3") (pintype "passive"))
      (node (ref "R129") (pin "1") (pinfunction "1_1") (pintype "passive"))
    )
    (net (code "29") (name "/ADC_DIG_SENSE_P") (class "Default")
      (node (ref "R125") (pin "4") (pinfunction "4_4") (pintype "passive"))
      (node (ref "R133") (pin "1") (pinfunction "1_1") (pintype "passive"))
    )
    (net (code "30") (name "/DRS4_OUT8_N") (class "Default")
      (node (ref "R127") (pin "1") (pinfunction "1_1") (pintype "passive"))
    )
    (net (code "31") (name "/DRS4_OUT8_P") (class "Default")
      (node (ref "R361") (pin "1") (pinfunction "1_1") (pintype "passive"))
    )
    (net (code "32") (name "/SCL_ADCINA226_AVDD") (class "Default")
      (node (ref "U43") (pin "1") (pinfunction "A1_1") (pintype "input"))
      (node (ref "U43") (pin "2") (pinfunction "A0_2") (pintype "input"))
      (node (ref "U43") (pin "5") (pinfunction "SCL_5") (pintype "input"))
    )
    (net (code "33") (name "/SCL_ADCINA226_DVDD") (class "Default")
      (node (ref "U41") (pin "5") (pinfunction "SCL_5") (pintype "input"))
    )
    (net (code "34") (name "/SCL_ADCTMP112") (class "Default")
      (node (ref "U42") (pin "1") (pinfunction "SCL_1") (pintype "input"))
    )
    (net (code "35") (name "/SDA_ADCINA226_AVDD") (class "Default")
      (node (ref "U43") (pin "4") (pinfunction "SDA_4") (pintype "bidirectional"))
    )
    (net (code "36") (name "/SDA_ADCINA226_DVDD") (class "Default")
      (node (ref "U41") (pin "2") (pinfunction "A0_2") (pintype "input"))
      (node (ref "U41") (pin "4") (pinfunction "SDA_4") (pintype "bidirectional"))
    )
    (net (code "37") (name "/SDA_ADCTMP112") (class "Default")
      (node (ref "U42") (pin "4") (pinfunction "ADD0_4") (pintype "input"))
      (node (ref "U42") (pin "6") (pinfunction "SDA_6") (pintype "bidirectional"))
    )
    (net (code "43") (name "2V5 ADC") (class "Default")
      (node (ref "C186") (pin "2") (pinfunction "2_2") (pintype "passive"))
      (node (ref "C187") (pin "1") (pinfunction "1_1") (pintype "passive"))
      (node (ref "C188") (pin "1") (pinfunction "1_1") (pintype "passive"))
      (node (ref "C189") (pin "1") (pinfunction "1_1") (pintype "passive"))
      (node (ref "C190") (pin "2") (pinfunction "2_2") (pintype "passive"))
      (node (ref "C191") (pin "2") (pinfunction "2_2") (pintype "passive"))
      (node (ref "C192") (pin "1") (pinfunction "1_1") (pintype "passive"))
      (node (ref "C193") (pin "1") (pinfunction "1_1") (pintype "passive"))
      (node (ref "C194") (pin "2") (pinfunction "2_2") (pintype "passive"))
      (node (ref "C195") (pin "2") (pinfunction "2_2") (pintype "passive"))
      (node (ref "C198") (pin "1") (pinfunction "1_1") (pintype "passive"))
      (node (ref "FB16") (pin "2") (pinfunction "2_2") (pintype "passive"))
      (node (ref "U40") (pin "16") (pinfunction "DRVDD_16") (pintype "power_in"))
    )
    (net (code "44") (name "2V5_ADC_DIG") (class "Default")
      (node (ref "R125") (pin "1") (pinfunction "1_1") (pintype "passive"))
      (node (ref "U41") (pin "8") (pinfunction "VBUS_8") (pintype "input"))
    )
    (net (code "45") (name "3.3V") (class "Default")
      (node (ref "C177") (pin "2") (pinfunction "2_2") (pintype "passive"))
      (node (ref "C178") (pin "2") (pinfunction "2_2") (pintype "passive"))
      (node (ref "C180") (pin "1") (pinfunction "1_1") (pintype "passive"))
      (node (ref "C181") (pin "2") (pinfunction "2_2") (pintype "passive"))
      (node (ref "C182") (pin "2") (pinfunction "2_2") (pintype "passive"))
      (node (ref "Q16") (pin "2") (pinfunction "E_2") (pintype "passive"))
      (node (ref "Q17") (pin "2") (pinfunction "E_2") (pintype "passive"))
      (node (ref "Q18") (pin "2") (pinfunction "E_2") (pintype "passive"))
      (node (ref "R131") (pin "2") (pinfunction "2_2") (pintype "passive"))
      (node (ref "R148") (pin "2") (pinfunction "2_2") (pintype "passive"))
      (node (ref "R152") (pin "2") (pinfunction "2_2") (pintype "passive"))
      (node (ref "U41") (pin "6") (pinfunction "VS+_6") (pintype "input"))
      (node (ref "U42") (pin "5") (pinfunction "V+_5") (pintype "power_in"))
      (node (ref "U43") (pin "6") (pinfunction "VS+_6") (pintype "input"))
    )
    (net (code "46") (name "3V ADC") (class "Default")
      (node (ref "C183") (pin "1") (pinfunction "1_1") (pintype "passive"))
      (node (ref "C184") (pin "2") (pinfunction "2_2") (pintype "passive"))
      (node (ref "C185") (pin "1") (pinfunction "1_1") (pintype "passive"))
      (node (ref "C196") (pin "2") (pinfunction "2_2") (pintype "passive"))
      (node (ref "C197") (pin "1") (pinfunction "1_1") (pintype "passive"))
      (node (ref "FB11") (pin "2") (pinfunction "2_2") (pintype "passive"))
      (node (ref "U40") (pin "27") (pinfunction "AVDD_27") (pintype "power_in"))
      (node (ref "U40") (pin "32") (pinfunction "AVDD_32") (pintype "power_in"))
    )
    (net (code "47") (name "3V_ADC_ANA") (class "Default")
      (node (ref "R144") (pin "1") (pinfunction "1_1") (pintype "passive"))
      (node (ref "U43") (pin "8") (pinfunction "VBUS_8") (pintype "input"))
    )
    (net (code "48") (name "ADC_AVDD") (class "Default")
      (node (ref "FB11") (pin "1") (pinfunction "1_1") (pintype "passive"))
      (node (ref "R144") (pin "2") (pinfunction "2_2") (pintype "passive"))
    )
    (net (code "49") (name "ADC_DVDD") (class "Default")
      (node (ref "FB16") (pin "1") (pinfunction "1_1") (pintype "passive"))
      (node (ref "R125") (pin "2") (pinfunction "2_2") (pintype "passive"))
    )
    (net (code "50") (name "Net-(C170-Pad2)") (class "Default")
      (node (ref "C170") (pin "2") (pinfunction "2_2") (pintype "passive"))
      (node (ref "R126") (pin "1") (pinfunction "1_1") (pintype "passive"))
    )
    (net (code "51") (name "Net-(D27-A)") (class "Default")
      (node (ref "D27") (pin "2") (pinfunction "A_2") (pintype "passive"))
      (node (ref "Q16") (pin "3") (pinfunction "C_3") (pintype "passive"))
    )
    (net (code "52") (name "Net-(D27-K)") (class "Default")
      (node (ref "D27") (pin "1") (pinfunction "K_1") (pintype "passive"))
      (node (ref "R140") (pin "2") (pinfunction "2_2") (pintype "passive"))
    )
    (net (code "53") (name "Net-(D28-A)") (class "Default")
      (node (ref "D28") (pin "2") (pinfunction "A_2") (pintype "passive"))
      (node (ref "Q17") (pin "3") (pinfunction "C_3") (pintype "passive"))
    )
    (net (code "54") (name "Net-(D28-K)") (class "Default")
      (node (ref "D28") (pin "1") (pinfunction "K_1") (pintype "passive"))
      (node (ref "R154") (pin "2") (pinfunction "2_2") (pintype "passive"))
    )
    (net (code "55") (name "Net-(D29-A)") (class "Default")
      (node (ref "D29") (pin "2") (pinfunction "A_2") (pintype "passive"))
      (node (ref "Q18") (pin "3") (pinfunction "C_3") (pintype "passive"))
    )
    (net (code "56") (name "Net-(D29-K)") (class "Default")
      (node (ref "D29") (pin "1") (pinfunction "K_1") (pintype "passive"))
      (node (ref "R155") (pin "2") (pinfunction "2_2") (pintype "passive"))
    )
    (net (code "57") (name "Net-(Q16-B)") (class "Default")
      (node (ref "Q16") (pin "1") (pinfunction "B_1") (pintype "passive"))
      (node (ref "R131") (pin "1") (pinfunction "1_1") (pintype "passive"))
      (node (ref "R135") (pin "1") (pinfunction "1_1") (pintype "passive"))
    )
    (net (code "58") (name "Net-(Q17-B)") (class "Default")
      (node (ref "Q17") (pin "1") (pinfunction "B_1") (pintype "passive"))
      (node (ref "R148") (pin "1") (pinfunction "1_1") (pintype "passive"))
      (node (ref "R150") (pin "1") (pinfunction "1_1") (pintype "passive"))
    )
    (net (code "59") (name "Net-(Q18-B)") (class "Default")
      (node (ref "Q18") (pin "1") (pinfunction "B_1") (pintype "passive"))
      (node (ref "R152") (pin "1") (pinfunction "1_1") (pintype "passive"))
      (node (ref "R153") (pin "1") (pinfunction "1_1") (pintype "passive"))
    )
    (net (code "60") (name "Net-(U40-REFB)") (class "Default")
      (node (ref "C172") (pin "2") (pinfunction "2_2") (pintype "passive"))
      (node (ref "C173") (pin "2") (pinfunction "2_2") (pintype "passive"))
      (node (ref "C174") (pin "2") (pinfunction "2_2") (pintype "passive"))
      (node (ref "U40") (pin "25") (pinfunction "REFB_25") (pintype "input"))
    )
    (net (code "61") (name "Net-(U40-REFT)") (class "Default")
      (node (ref "C169") (pin "2") (pinfunction "2_2") (pintype "passive"))
      (node (ref "C172") (pin "1") (pinfunction "1_1") (pintype "passive"))
      (node (ref "C173") (pin "1") (pinfunction "1_1") (pintype "passive"))
      (node (ref "U40") (pin "26") (pinfunction "REFT_26") (pintype "input"))
    )
    (net (code "62") (name "Net-(U40-VREF)") (class "Default")
      (node (ref "C175") (pin "1") (pinfunction "1_1") (pintype "passive"))
      (node (ref "C176") (pin "1") (pinfunction "1_1") (pintype "passive"))
      (node (ref "U40") (pin "24") (pinfunction "VREF_24") (pintype "input"))
    )
    (net (code "63") (name "Net-(U41-ALERT)") (class "Default")
      (node (ref "R135") (pin "2") (pinfunction "2_2") (pintype "passive"))
      (node (ref "U41") (pin "3") (pinfunction "ALERT_3") (pintype "open_collector"))
    )
    (net (code "64") (name "Net-(U41-VIN+)") (class "Default")
      (node (ref "C171") (pin "1") (pinfunction "1_1") (pintype "passive"))
      (node (ref "R133") (pin "2") (pinfunction "2_2") (pintype "passive"))
      (node (ref "U41") (pin "10") (pinfunction "VIN+_10") (pintype "input"))
    )
    (net (code "65") (name "Net-(U41-VIN-)") (class "Default")
      (node (ref "C171") (pin "2") (pinfunction "2_2") (pintype "passive"))
      (node (ref "R129") (pin "2") (pinfunction "2_2") (pintype "passive"))
      (node (ref "U41") (pin "9") (pinfunction "VIN-_9") (pintype "input"))
    )
    (net (code "66") (name "Net-(U42-ALERT)") (class "Default")
      (node (ref "R150") (pin "2") (pinfunction "2_2") (pintype "passive"))
      (node (ref "U42") (pin "3") (pinfunction "ALERT_3") (pintype "open_collector"))
    )
    (net (code "67") (name "Net-(U43-ALERT)") (class "Default")
      (node (ref "R153") (pin "2") (pinfunction "2_2") (pintype "passive"))
      (node (ref "U43") (pin "3") (pinfunction "ALERT_3") (pintype "open_collector"))
    )
    (net (code "68") (name "Net-(U43-VIN+)") (class "Default")
      (node (ref "C179") (pin "1") (pinfunction "1_1") (pintype "passive"))
      (node (ref "R151") (pin "2") (pinfunction "2_2") (pintype "passive"))
      (node (ref "U43") (pin "10") (pinfunction "VIN+_10") (pintype "input"))
    )
    (net (code "69") (name "Net-(U43-VIN-)") (class "Default")
      (node (ref "C179") (pin "2") (pinfunction "2_2") (pintype "passive"))
      (node (ref "R149") (pin "2") (pinfunction "2_2") (pintype "passive"))
      (node (ref "U43") (pin "9") (pinfunction "VIN-_9") (pintype "input"))
    )
    (net (code "70") (name "TRB_GND") (class "Default")
      (node (ref "C123") (pin "2") (pinfunction "2_2") (pintype "passive"))
      (node (ref "C124") (pin "2") (pinfunction "2_2") (pintype "passive"))
      (node (ref "C169") (pin "1") (pinfunction "1_1") (pintype "passive"))
      (node (ref "C170") (pin "1") (pinfunction "1_1") (pintype "passive"))
      (node (ref "C174") (pin "1") (pinfunction "1_1") (pintype "passive"))
      (node (ref "C175") (pin "2") (pinfunction "2_2") (pintype "passive"))
      (node (ref "C176") (pin "2") (pinfunction "2_2") (pintype "passive"))
      (node (ref "C177") (pin "1") (pinfunction "1_1") (pintype "passive"))
      (node (ref "C178") (pin "1") (pinfunction "1_1") (pintype "passive"))
      (node (ref "C180") (pin "2") (pinfunction "2_2") (pintype "passive"))
      (node (ref "C181") (pin "1") (pinfunction "1_1") (pintype "passive"))
      (node (ref "C182") (pin "1") (pinfunction "1_1") (pintype "passive"))
      (node (ref "C183") (pin "2") (pinfunction "2_2") (pintype "passive"))
      (node (ref "C184") (pin "1") (pinfunction "1_1") (pintype "passive"))
      (node (ref "C185") (pin "2") (pinfunction "2_2") (pintype "passive"))
      (node (ref "C186") (pin "1") (pinfunction "1_1") (pintype "passive"))
      (node (ref "C187") (pin "2") (pinfunction "2_2") (pintype "passive"))
      (node (ref "C188") (pin "2") (pinfunction "2_2") (pintype "passive"))
      (node (ref "C189") (pin "2") (pinfunction "2_2") (pintype "passive"))
      (node (ref "C190") (pin "1") (pinfunction "1_1") (pintype "passive"))
      (node (ref "C191") (pin "1") (pinfunction "1_1") (pintype "passive"))
      (node (ref "C192") (pin "2") (pinfunction "2_2") (pintype "passive"))
      (node (ref "C193") (pin "2") (pinfunction "2_2") (pintype "passive"))
      (node (ref "C194") (pin "1") (pinfunction "1_1") (pintype "passive"))
      (node (ref "C195") (pin "1") (pinfunction "1_1") (pintype "passive"))
      (node (ref "C196") (pin "1") (pinfunction "1_1") (pintype "passive"))
      (node (ref "C197") (pin "2") (pinfunction "2_2") (pintype "passive"))
      (node (ref "C198") (pin "2") (pinfunction "2_2") (pintype "passive"))
      (node (ref "R140") (pin "1") (pinfunction "1_1") (pintype "passive"))
      (node (ref "R154") (pin "1") (pinfunction "1_1") (pintype "passive"))
      (node (ref "R155") (pin "1") (pinfunction "1_1") (pintype "passive"))
      (node (ref "U40") (pin "15") (pinfunction "DGND_15") (pintype "passive"))
      (node (ref "U40") (pin "22") (pinfunction "MODE_22") (pintype "input"))
      (node (ref "U40") (pin "23") (pinfunction "SENSE_23") (pintype "input"))
      (node (ref "U40") (pin "28") (pinfunction "AGND_28") (pintype "passive"))
      (node (ref "U40") (pin "31") (pinfunction "AGND_31") (pintype "passive"))
      (node (ref "U40") (pin "33") (pinfunction "EP_33") (pintype "passive"))
      (node (ref "U40") (pin "4") (pinfunction "PDWN_4") (pintype "input"))
      (node (ref "U41") (pin "1") (pinfunction "A1_1") (pintype "input"))
      (node (ref "U41") (pin "7") (pinfunction "GND_7") (pintype "power_in"))
      (node (ref "U42") (pin "2") (pinfunction "GND_2") (pintype "power_in"))
      (node (ref "U43") (pin "7") (pinfunction "GND_7") (pintype "power_in"))
    )
    (net (code "71") (name "unconnected-(R128-Pad2)") (class "Default")
      (node (ref "R128") (pin "2") (pinfunction "2_2") (pintype "passive"))
    )
    (net (code "72") (name "unconnected-(R130-Pad2)") (class "Default")
      (node (ref "R130") (pin "2") (pinfunction "2_2") (pintype "passive"))
    )
    (net (code "73") (name "unconnected-(R132-Pad2)") (class "Default")
      (node (ref "R132") (pin "2") (pinfunction "2_2") (pintype "passive"))
    )
    (net (code "74") (name "unconnected-(R134-Pad2)") (class "Default")
      (node (ref "R134") (pin "2") (pinfunction "2_2") (pintype "passive"))
    )
    (net (code "75") (name "unconnected-(R136-Pad2)") (class "Default")
      (node (ref "R136") (pin "2") (pinfunction "2_2") (pintype "passive"))
    )
    (net (code "76") (name "unconnected-(R137-Pad2)") (class "Default")
      (node (ref "R137") (pin "2") (pinfunction "2_2") (pintype "passive"))
    )
    (net (code "77") (name "unconnected-(R138-Pad2)") (class "Default")
      (node (ref "R138") (pin "2") (pinfunction "2_2") (pintype "passive"))
    )
    (net (code "78") (name "unconnected-(R139-Pad2)") (class "Default")
      (node (ref "R139") (pin "2") (pinfunction "2_2") (pintype "passive"))
    )
    (net (code "79") (name "unconnected-(R141-Pad2)") (class "Default")
      (node (ref "R141") (pin "2") (pinfunction "2_2") (pintype "passive"))
    )
    (net (code "80") (name "unconnected-(R142-Pad2)") (class "Default")
      (node (ref "R142") (pin "2") (pinfunction "2_2") (pintype "passive"))
    )
    (net (code "81") (name "unconnected-(R143-Pad2)") (class "Default")
      (node (ref "R143") (pin "2") (pinfunction "2_2") (pintype "passive"))
    )
    (net (code "82") (name "unconnected-(R145-Pad2)") (class "Default")
      (node (ref "R145") (pin "2") (pinfunction "2_2") (pintype "passive"))
    )
    (net (code "83") (name "unconnected-(R146-Pad2)") (class "Default")
      (node (ref "R146") (pin "2") (pinfunction "2_2") (pintype "passive"))
    )
    (net (code "84") (name "unconnected-(R147-Pad2)") (class "Default")
      (node (ref "R147") (pin "2") (pinfunction "2_2") (pintype "passive"))
    )
    (net (code "85") (name "unconnected-(U40-DNC-Pad1)") (class "Default")
      (node (ref "U40") (pin "1") (pinfunction "DNC_1") (pintype "passive+no_connect"))
    )
    (net (code "86") (name "unconnected-(U40-DNC-Pad3)") (class "Default")
      (node (ref "U40") (pin "3") (pinfunction "DNC_3") (pintype "passive+no_connect"))
    )
    (net (code "87") (name "unconnected-(U40-OTR-Pad21)") (class "Default")
      (node (ref "U40") (pin "21") (pinfunction "OTR_21") (pintype "output+no_connect"))
    )
  )
)
